# ig-normal-ver12.net
KiCad netlist of a schematic drawn in EAGLE
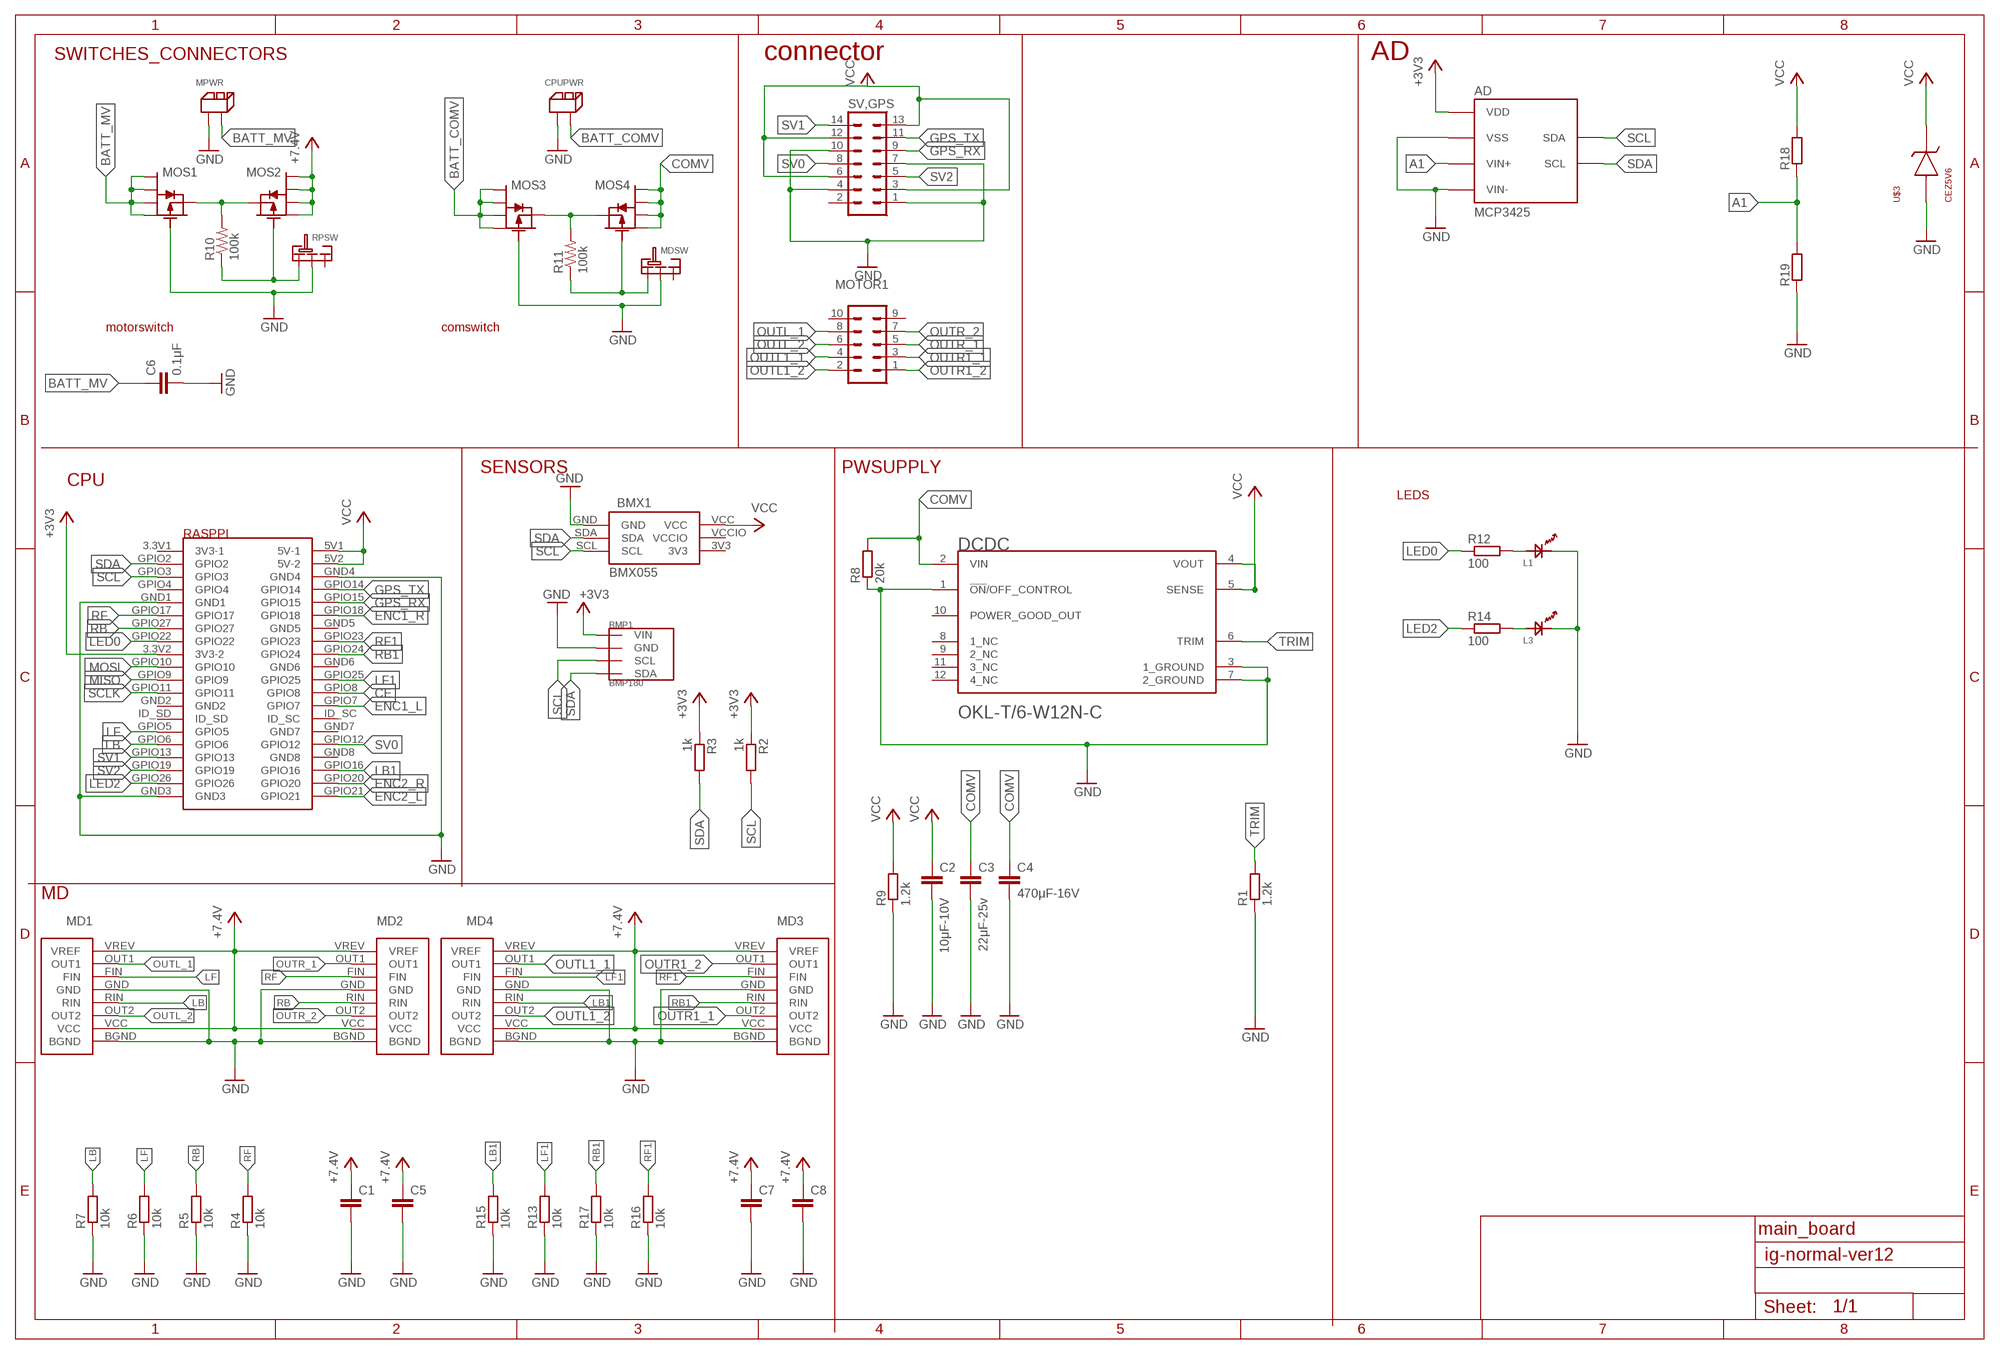
[diagram p0: schematic, sheet 1]

(export (version "E")
  (design (tool "Eeschema 10.0.6"))
  (components
    (comp (ref "AD")
      (value "MCP3425")
      (footprint "eagle-import:SOT23-6")
      (libsource (lib "eagle-import") (part "MCP3425"))
    )
    (comp (ref "BMP1")
      (value "BMP180")
      (footprint "eagle-import:GY-68")
      (libsource (lib "eagle-import") (part "BMP180"))
    )
    (comp (ref "BMX1")
      (value "BMX055")
      (footprint "eagle-import:BMX055")
      (libsource (lib "eagle-import") (part "BMX055"))
    )
    (comp (ref "C1")
      (value "C-EUC0603")
      (footprint "eagle-import:C0603")
      (libsource (lib "eagle-import") (part "C-EUC0603"))
    )
    (comp (ref "C2")
      (value "10μF-10V")
      (footprint "eagle-import:C0603")
      (libsource (lib "eagle-import") (part "C-EUC0603"))
    )
    (comp (ref "C3")
      (value "22μF-25v")
      (footprint "eagle-import:C0805")
      (libsource (lib "eagle-import") (part "C-EUC0805"))
    )
    (comp (ref "C4")
      (value "470μF-16V")
      (footprint "eagle-import:C0603")
      (libsource (lib "eagle-import") (part "C-EUC0603"))
    )
    (comp (ref "C5")
      (value "C-EUC0603")
      (footprint "eagle-import:C0603")
      (libsource (lib "eagle-import") (part "C-EUC0603"))
    )
    (comp (ref "C6")
      (value "0.1μF")
      (footprint "eagle-import:C0603")
      (libsource (lib "eagle-import") (part "C-EUC0603"))
    )
    (comp (ref "C7")
      (value "C-EUC0603")
      (footprint "eagle-import:C0603")
      (libsource (lib "eagle-import") (part "C-EUC0603"))
    )
    (comp (ref "C8")
      (value "C-EUC0603")
      (footprint "eagle-import:C0603")
      (libsource (lib "eagle-import") (part "C-EUC0603"))
    )
    (comp (ref "CPUPWR")
      (value "2PIN")
      (footprint "eagle-import:2PIN")
      (libsource (lib "eagle-import") (part "2PIN"))
    )
    (comp (ref "DCDC")
      (value "OKL-T/6-W12N-CMURATA_OKL-T-6-W12N-C_0_0")
      (footprint "eagle-import:MURATA_OKL-T-6-W12N-C_0")
      (fields
        (field (name "DIGIKEY_PART_NUMBER") "811-2214-1-ND")
        (field (name "MF") "Murata")
        (field (name "MOUSER_PART_NUMBER") "580-OKL-T/6-W12N-C")
      )
      (libsource (lib "eagle-import") (part "OKL-T/6-W12N-CMURATA_OKL-T-6-W12N-C_0_0"))
    )
    (comp (ref "L1")
      (value "OSXX1608C1A")
      (footprint "eagle-import:OSXX1608C1A")
      (libsource (lib "eagle-import") (part "OSXX1608C1A"))
    )
    (comp (ref "L3")
      (value "OSXX1608C1A")
      (footprint "eagle-import:OSXX1608C1A")
      (libsource (lib "eagle-import") (part "OSXX1608C1A"))
    )
    (comp (ref "MD1")
      (value "BD6222HFP-TR")
      (footprint "eagle-import:BD6222HFP-TR")
      (libsource (lib "eagle-import") (part "BD6222HFP-TR"))
    )
    (comp (ref "MD2")
      (value "BD6222HFP-TR")
      (footprint "eagle-import:BD6222HFP-TR")
      (libsource (lib "eagle-import") (part "BD6222HFP-TR"))
    )
    (comp (ref "MD3")
      (value "BD6222HFP-TR")
      (footprint "eagle-import:BD6222HFP-TR")
      (libsource (lib "eagle-import") (part "BD6222HFP-TR"))
    )
    (comp (ref "MD4")
      (value "BD6222HFP-TR")
      (footprint "eagle-import:BD6222HFP-TR")
      (libsource (lib "eagle-import") (part "BD6222HFP-TR"))
    )
    (comp (ref "MDSW")
      (value "SRIDE_SWITCH")
      (footprint "eagle-import:SRIDE_SWITCH")
      (libsource (lib "eagle-import") (part "SRIDE_SWITCH"))
    )
    (comp (ref "MOS1")
      (value "PCH_SSM6J808R")
      (footprint "eagle-import:SSM6J808R")
      (libsource (lib "eagle-import") (part "PCH_SSM6J808R"))
    )
    (comp (ref "MOS2")
      (value "PCH_SSM6J808R")
      (footprint "eagle-import:SSM6J808R")
      (libsource (lib "eagle-import") (part "PCH_SSM6J808R"))
    )
    (comp (ref "MOS3")
      (value "PCH_SSM6J808R")
      (footprint "eagle-import:SSM6J808R")
      (libsource (lib "eagle-import") (part "PCH_SSM6J808R"))
    )
    (comp (ref "MOS4")
      (value "PCH_SSM6J808R")
      (footprint "eagle-import:SSM6J808R")
      (libsource (lib "eagle-import") (part "PCH_SSM6J808R"))
    )
    (comp (ref "MOTOR1")
      (value "ML10L")
      (footprint "eagle-import:ML10L")
      (libsource (lib "eagle-import") (part "ML10L"))
    )
    (comp (ref "MPWR")
      (value "2PIN")
      (footprint "eagle-import:2PIN")
      (libsource (lib "eagle-import") (part "2PIN"))
    )
    (comp (ref "R1")
      (value "1.2k")
      (footprint "eagle-import:R0805")
      (libsource (lib "eagle-import") (part "R-EU_R0805"))
    )
    (comp (ref "R2")
      (value "1k")
      (footprint "eagle-import:R0603")
      (libsource (lib "eagle-import") (part "R-EU_R0603"))
    )
    (comp (ref "R3")
      (value "1k")
      (footprint "eagle-import:R0603")
      (libsource (lib "eagle-import") (part "R-EU_R0603"))
    )
    (comp (ref "R4")
      (value "10k")
      (footprint "eagle-import:R0603")
      (libsource (lib "eagle-import") (part "R-EU_R0603"))
    )
    (comp (ref "R5")
      (value "10k")
      (footprint "eagle-import:R0603")
      (libsource (lib "eagle-import") (part "R-EU_R0603"))
    )
    (comp (ref "R6")
      (value "10k")
      (footprint "eagle-import:R0603")
      (libsource (lib "eagle-import") (part "R-EU_R0603"))
    )
    (comp (ref "R7")
      (value "10k")
      (footprint "eagle-import:R0603")
      (libsource (lib "eagle-import") (part "R-EU_R0603"))
    )
    (comp (ref "R8")
      (value "20k")
      (footprint "eagle-import:R0603")
      (libsource (lib "eagle-import") (part "R-EU_R0603"))
    )
    (comp (ref "R9")
      (value "1.2k")
      (footprint "eagle-import:R0805")
      (libsource (lib "eagle-import") (part "R-EU_R0805"))
    )
    (comp (ref "R10")
      (value "100k")
      (footprint "eagle-import:R0603")
      (libsource (lib "eagle-import") (part "R-US_R0603"))
    )
    (comp (ref "R11")
      (value "100k")
      (footprint "eagle-import:R0603")
      (libsource (lib "eagle-import") (part "R-US_R0603"))
    )
    (comp (ref "R12")
      (value "100")
      (footprint "eagle-import:R0603")
      (libsource (lib "eagle-import") (part "R-EU_R0603"))
    )
    (comp (ref "R13")
      (value "10k")
      (footprint "eagle-import:R0603")
      (libsource (lib "eagle-import") (part "R-EU_R0603"))
    )
    (comp (ref "R14")
      (value "100")
      (footprint "eagle-import:R0603")
      (libsource (lib "eagle-import") (part "R-EU_R0603"))
    )
    (comp (ref "R15")
      (value "10k")
      (footprint "eagle-import:R0603")
      (libsource (lib "eagle-import") (part "R-EU_R0603"))
    )
    (comp (ref "R16")
      (value "10k")
      (footprint "eagle-import:R0603")
      (libsource (lib "eagle-import") (part "R-EU_R0603"))
    )
    (comp (ref "R17")
      (value "10k")
      (footprint "eagle-import:R0603")
      (libsource (lib "eagle-import") (part "R-EU_R0603"))
    )
    (comp (ref "R18")
      (value "R-EU_R0603")
      (footprint "eagle-import:R0603")
      (libsource (lib "eagle-import") (part "R-EU_R0603"))
    )
    (comp (ref "R19")
      (value "R-EU_R0603")
      (footprint "eagle-import:R0603")
      (libsource (lib "eagle-import") (part "R-EU_R0603"))
    )
    (comp (ref "RASPPI")
      (value "RASPBERYPIZEROW")
      (footprint "eagle-import:RASPBERYPIZEROW")
      (libsource (lib "eagle-import") (part "RASPBERYPIZEROW"))
    )
    (comp (ref "RPSW")
      (value "SRIDE_SWITCH")
      (footprint "eagle-import:SRIDE_SWITCH")
      (libsource (lib "eagle-import") (part "SRIDE_SWITCH"))
    )
    (comp (ref "SV,GPS")
      (value "ML14L")
      (footprint "eagle-import:ML14L")
      (libsource (lib "eagle-import") (part "ML14L"))
    )
    (comp (ref "U$3")
      (value "CEZ5V6")
      (footprint "eagle-import:CEZ5V6")
      (libsource (lib "eagle-import") (part "CEZ5V6"))
    )
  )
  (nets
    (net (code "1") (name "+3V3") (class "Default")
      (node (ref "AD") (pin "5") (pinfunction "VDD_5") (pintype "power_in"))
      (node (ref "BMP1") (pin "P1") (pinfunction "VIN_P1") (pintype "bidirectional"))
      (node (ref "R2") (pin "1") (pinfunction "1_1") (pintype "passive"))
      (node (ref "R3") (pin "1") (pinfunction "1_1") (pintype "passive"))
      (node (ref "RASPPI") (pin "3.3V2") (pinfunction "3V3-2_3.3V2") (pintype "bidirectional"))
    )
    (net (code "2") (name "+7.4V") (class "Default")
      (node (ref "C1") (pin "1") (pinfunction "1_1") (pintype "passive"))
      (node (ref "C5") (pin "1") (pinfunction "1_1") (pintype "passive"))
      (node (ref "C7") (pin "1") (pinfunction "1_1") (pintype "passive"))
      (node (ref "C8") (pin "1") (pinfunction "1_1") (pintype "passive"))
      (node (ref "MD1") (pin "VCC") (pinfunction "VCC_VCC") (pintype "bidirectional"))
      (node (ref "MD1") (pin "VREV") (pinfunction "VREF_VREV") (pintype "bidirectional"))
      (node (ref "MD2") (pin "VCC") (pinfunction "VCC_VCC") (pintype "bidirectional"))
      (node (ref "MD2") (pin "VREV") (pinfunction "VREF_VREV") (pintype "bidirectional"))
      (node (ref "MD3") (pin "VCC") (pinfunction "VCC_VCC") (pintype "bidirectional"))
      (node (ref "MD3") (pin "VREV") (pinfunction "VREF_VREV") (pintype "bidirectional"))
      (node (ref "MD4") (pin "VCC") (pinfunction "VCC_VCC") (pintype "bidirectional"))
      (node (ref "MD4") (pin "VREV") (pinfunction "VREF_VREV") (pintype "bidirectional"))
      (node (ref "MOS2") (pin "1") (pinfunction "1_1") (pintype "bidirectional"))
      (node (ref "MOS2") (pin "2") (pinfunction "2_2") (pintype "bidirectional"))
      (node (ref "MOS2") (pin "5") (pinfunction "5_5") (pintype "bidirectional"))
      (node (ref "MOS2") (pin "6") (pinfunction "6_6") (pintype "bidirectional"))
    )
    (net (code "3") (name "/3V3") (class "Default")
      (node (ref "BMX1") (pin "3V3") (pinfunction "3V3_3V3") (pintype "power_in"))
    )
    (net (code "4") (name "/VCCIO") (class "Default")
      (node (ref "BMX1") (pin "VCCIO") (pinfunction "VCCIO_VCCIO") (pintype "power_in"))
    )
    (net (code "5") (name "A1") (class "Default")
      (node (ref "AD") (pin "1") (pinfunction "VIN+_1") (pintype "input"))
      (node (ref "R18") (pin "1") (pinfunction "1_1") (pintype "passive"))
      (node (ref "R19") (pin "2") (pinfunction "2_2") (pintype "passive"))
    )
    (net (code "6") (name "BATT_COMV") (class "Default")
      (node (ref "CPUPWR") (pin "P$2") (pinfunction "P$2_P$2") (pintype "bidirectional"))
      (node (ref "MOS3") (pin "1") (pinfunction "1_1") (pintype "bidirectional"))
      (node (ref "MOS3") (pin "2") (pinfunction "2_2") (pintype "bidirectional"))
      (node (ref "MOS3") (pin "5") (pinfunction "5_5") (pintype "bidirectional"))
      (node (ref "MOS3") (pin "6") (pinfunction "6_6") (pintype "bidirectional"))
    )
    (net (code "7") (name "BATT_MV") (class "Default")
      (node (ref "C6") (pin "1") (pinfunction "1_1") (pintype "passive"))
      (node (ref "MOS1") (pin "1") (pinfunction "1_1") (pintype "bidirectional"))
      (node (ref "MOS1") (pin "2") (pinfunction "2_2") (pintype "bidirectional"))
      (node (ref "MOS1") (pin "5") (pinfunction "5_5") (pintype "bidirectional"))
      (node (ref "MOS1") (pin "6") (pinfunction "6_6") (pintype "bidirectional"))
      (node (ref "MPWR") (pin "P$2") (pinfunction "P$2_P$2") (pintype "bidirectional"))
    )
    (net (code "8") (name "CE") (class "Default")
      (node (ref "RASPPI") (pin "GPIO8") (pinfunction "GPIO8_GPIO8") (pintype "bidirectional"))
    )
    (net (code "9") (name "COMV") (class "Default")
      (node (ref "C3") (pin "1") (pinfunction "1_1") (pintype "passive"))
      (node (ref "C4") (pin "1") (pinfunction "1_1") (pintype "passive"))
      (node (ref "DCDC") (pin "2") (pinfunction "VIN_2") (pintype "bidirectional"))
      (node (ref "MOS4") (pin "1") (pinfunction "1_1") (pintype "bidirectional"))
      (node (ref "MOS4") (pin "2") (pinfunction "2_2") (pintype "bidirectional"))
      (node (ref "MOS4") (pin "5") (pinfunction "5_5") (pintype "bidirectional"))
      (node (ref "MOS4") (pin "6") (pinfunction "6_6") (pintype "bidirectional"))
      (node (ref "R8") (pin "2") (pinfunction "2_2") (pintype "passive"))
    )
    (net (code "10") (name "ENC1_L") (class "Default")
      (node (ref "RASPPI") (pin "GPIO7") (pinfunction "GPIO7_GPIO7") (pintype "bidirectional"))
    )
    (net (code "11") (name "ENC1_R") (class "Default")
      (node (ref "RASPPI") (pin "GPIO18") (pinfunction "GPIO18_GPIO18") (pintype "bidirectional"))
    )
    (net (code "12") (name "ENC2_L") (class "Default")
      (node (ref "RASPPI") (pin "GPIO21") (pinfunction "GPIO21_GPIO21") (pintype "bidirectional"))
    )
    (net (code "13") (name "ENC2_R") (class "Default")
      (node (ref "RASPPI") (pin "GPIO20") (pinfunction "GPIO20_GPIO20") (pintype "bidirectional"))
    )
    (net (code "14") (name "GND") (class "Default")
      (node (ref "AD") (pin "2") (pinfunction "VSS_2") (pintype "power_in"))
      (node (ref "AD") (pin "6") (pinfunction "VIN-_6") (pintype "input"))
      (node (ref "BMP1") (pin "P2") (pinfunction "GND_P2") (pintype "bidirectional"))
      (node (ref "BMX1") (pin "GND") (pinfunction "GND_GND") (pintype "power_in"))
      (node (ref "C1") (pin "2") (pinfunction "2_2") (pintype "passive"))
      (node (ref "C2") (pin "2") (pinfunction "2_2") (pintype "passive"))
      (node (ref "C3") (pin "2") (pinfunction "2_2") (pintype "passive"))
      (node (ref "C4") (pin "2") (pinfunction "2_2") (pintype "passive"))
      (node (ref "C5") (pin "2") (pinfunction "2_2") (pintype "passive"))
      (node (ref "C6") (pin "2") (pinfunction "2_2") (pintype "passive"))
      (node (ref "C7") (pin "2") (pinfunction "2_2") (pintype "passive"))
      (node (ref "C8") (pin "2") (pinfunction "2_2") (pintype "passive"))
      (node (ref "CPUPWR") (pin "P$1") (pinfunction "P$1_P$1") (pintype "bidirectional"))
      (node (ref "DCDC") (pin "1") (pinfunction "~{ON}/OFF_CONTROL_1") (pintype "bidirectional"))
      (node (ref "DCDC") (pin "3") (pinfunction "1_GROUND_3") (pintype "power_in"))
      (node (ref "DCDC") (pin "7") (pinfunction "2_GROUND_7") (pintype "power_in"))
      (node (ref "L1") (pin "CT") (pinfunction "CT_CT") (pintype "bidirectional"))
      (node (ref "L3") (pin "CT") (pinfunction "CT_CT") (pintype "bidirectional"))
      (node (ref "MD1") (pin "BGND") (pinfunction "BGND_BGND") (pintype "bidirectional"))
      (node (ref "MD1") (pin "GND") (pinfunction "GND_GND") (pintype "bidirectional"))
      (node (ref "MD2") (pin "BGND") (pinfunction "BGND_BGND") (pintype "bidirectional"))
      (node (ref "MD2") (pin "GND") (pinfunction "GND_GND") (pintype "bidirectional"))
      (node (ref "MD3") (pin "BGND") (pinfunction "BGND_BGND") (pintype "bidirectional"))
      (node (ref "MD3") (pin "GND") (pinfunction "GND_GND") (pintype "bidirectional"))
      (node (ref "MD4") (pin "BGND") (pinfunction "BGND_BGND") (pintype "bidirectional"))
      (node (ref "MD4") (pin "GND") (pinfunction "GND_GND") (pintype "bidirectional"))
      (node (ref "MDSW") (pin "LR") (pinfunction "LR_LR") (pintype "bidirectional"))
      (node (ref "MOS1") (pin "3") (pinfunction "3_3") (pintype "bidirectional"))
      (node (ref "MOS3") (pin "3") (pinfunction "3_3") (pintype "bidirectional"))
      (node (ref "MPWR") (pin "P$1") (pinfunction "P$1_P$1") (pintype "bidirectional"))
      (node (ref "R1") (pin "1") (pinfunction "1_1") (pintype "passive"))
      (node (ref "R13") (pin "1") (pinfunction "1_1") (pintype "passive"))
      (node (ref "R15") (pin "1") (pinfunction "1_1") (pintype "passive"))
      (node (ref "R16") (pin "1") (pinfunction "1_1") (pintype "passive"))
      (node (ref "R17") (pin "1") (pinfunction "1_1") (pintype "passive"))
      (node (ref "R19") (pin "1") (pinfunction "1_1") (pintype "passive"))
      (node (ref "R4") (pin "1") (pinfunction "1_1") (pintype "passive"))
      (node (ref "R5") (pin "1") (pinfunction "1_1") (pintype "passive"))
      (node (ref "R6") (pin "1") (pinfunction "1_1") (pintype "passive"))
      (node (ref "R7") (pin "1") (pinfunction "1_1") (pintype "passive"))
      (node (ref "R8") (pin "1") (pinfunction "1_1") (pintype "passive"))
      (node (ref "R9") (pin "1") (pinfunction "1_1") (pintype "passive"))
      (node (ref "RASPPI") (pin "GND1") (pinfunction "GND1_GND1") (pintype "bidirectional"))
      (node (ref "RASPPI") (pin "GND3") (pinfunction "GND3_GND3") (pintype "bidirectional"))
      (node (ref "RASPPI") (pin "GND4") (pinfunction "GND4_GND4") (pintype "bidirectional"))
      (node (ref "RPSW") (pin "LR") (pinfunction "LR_LR") (pintype "bidirectional"))
      (node (ref "SV,GPS") (pin "1") (pinfunction "1_1") (pintype "passive"))
      (node (ref "SV,GPS") (pin "10") (pinfunction "10_10") (pintype "passive"))
      (node (ref "SV,GPS") (pin "4") (pinfunction "4_4") (pintype "passive"))
      (node (ref "SV,GPS") (pin "7") (pinfunction "7_7") (pintype "passive"))
      (node (ref "U$3") (pin "P$1") (pinfunction "P$1_P$1") (pintype "bidirectional"))
    )
    (net (code "15") (name "GPS_RX") (class "Default")
      (node (ref "RASPPI") (pin "GPIO15") (pinfunction "GPIO15_GPIO15") (pintype "bidirectional"))
      (node (ref "SV,GPS") (pin "9") (pinfunction "9_9") (pintype "passive"))
    )
    (net (code "16") (name "GPS_TX") (class "Default")
      (node (ref "RASPPI") (pin "GPIO14") (pinfunction "GPIO14_GPIO14") (pintype "bidirectional"))
      (node (ref "SV,GPS") (pin "11") (pinfunction "11_11") (pintype "passive"))
    )
    (net (code "17") (name "LB") (class "Default")
      (node (ref "MD1") (pin "RIN") (pinfunction "RIN_RIN") (pintype "bidirectional"))
      (node (ref "R7") (pin "2") (pinfunction "2_2") (pintype "passive"))
      (node (ref "RASPPI") (pin "GPIO6") (pinfunction "GPIO6_GPIO6") (pintype "bidirectional"))
    )
    (net (code "18") (name "LB1") (class "Default")
      (node (ref "MD4") (pin "RIN") (pinfunction "RIN_RIN") (pintype "bidirectional"))
      (node (ref "R15") (pin "2") (pinfunction "2_2") (pintype "passive"))
      (node (ref "RASPPI") (pin "GPIO16") (pinfunction "GPIO16_GPIO16") (pintype "bidirectional"))
    )
    (net (code "19") (name "LED0") (class "Default")
      (node (ref "R12") (pin "1") (pinfunction "1_1") (pintype "passive"))
      (node (ref "RASPPI") (pin "GPIO22") (pinfunction "GPIO22_GPIO22") (pintype "bidirectional"))
    )
    (net (code "20") (name "LED2") (class "Default")
      (node (ref "R14") (pin "1") (pinfunction "1_1") (pintype "passive"))
      (node (ref "RASPPI") (pin "GPIO26") (pinfunction "GPIO26_GPIO26") (pintype "bidirectional"))
    )
    (net (code "21") (name "LF") (class "Default")
      (node (ref "MD1") (pin "FIN") (pinfunction "FIN_FIN") (pintype "bidirectional"))
      (node (ref "R6") (pin "2") (pinfunction "2_2") (pintype "passive"))
      (node (ref "RASPPI") (pin "GPIO5") (pinfunction "GPIO5_GPIO5") (pintype "bidirectional"))
    )
    (net (code "22") (name "LF1") (class "Default")
      (node (ref "MD4") (pin "FIN") (pinfunction "FIN_FIN") (pintype "bidirectional"))
      (node (ref "R13") (pin "2") (pinfunction "2_2") (pintype "passive"))
      (node (ref "RASPPI") (pin "GPIO25") (pinfunction "GPIO25_GPIO25") (pintype "bidirectional"))
    )
    (net (code "23") (name "MISO") (class "Default")
      (node (ref "RASPPI") (pin "GPIO9") (pinfunction "GPIO9_GPIO9") (pintype "bidirectional"))
    )
    (net (code "24") (name "MOSI") (class "Default")
      (node (ref "RASPPI") (pin "GPIO10") (pinfunction "GPIO10_GPIO10") (pintype "bidirectional"))
    )
    (net (code "25") (name "Net-(L1-PadAN)") (class "Default")
      (node (ref "L1") (pin "AN") (pinfunction "AN_AN") (pintype "bidirectional"))
      (node (ref "R12") (pin "2") (pinfunction "2_2") (pintype "passive"))
    )
    (net (code "26") (name "Net-(L3-PadAN)") (class "Default")
      (node (ref "L3") (pin "AN") (pinfunction "AN_AN") (pintype "bidirectional"))
      (node (ref "R14") (pin "2") (pinfunction "2_2") (pintype "passive"))
    )
    (net (code "27") (name "Net-(MDSW-PadL)") (class "Default")
      (node (ref "MDSW") (pin "L") (pinfunction "L_L") (pintype "bidirectional"))
      (node (ref "MOS4") (pin "3") (pinfunction "3_3") (pintype "bidirectional"))
      (node (ref "R11") (pin "1") (pinfunction "1_1") (pintype "passive"))
    )
    (net (code "28") (name "Net-(MOS1-Pad4)") (class "Default")
      (node (ref "MOS1") (pin "4") (pinfunction "4_4") (pintype "bidirectional"))
      (node (ref "MOS2") (pin "4") (pinfunction "4_4") (pintype "bidirectional"))
      (node (ref "R10") (pin "2") (pinfunction "2_2") (pintype "passive"))
    )
    (net (code "29") (name "Net-(MOS2-Pad3)") (class "Default")
      (node (ref "MOS2") (pin "3") (pinfunction "3_3") (pintype "bidirectional"))
      (node (ref "R10") (pin "1") (pinfunction "1_1") (pintype "passive"))
      (node (ref "RPSW") (pin "L") (pinfunction "L_L") (pintype "bidirectional"))
    )
    (net (code "30") (name "Net-(MOS3-Pad4)") (class "Default")
      (node (ref "MOS3") (pin "4") (pinfunction "4_4") (pintype "bidirectional"))
      (node (ref "MOS4") (pin "4") (pinfunction "4_4") (pintype "bidirectional"))
      (node (ref "R11") (pin "2") (pinfunction "2_2") (pintype "passive"))
    )
    (net (code "31") (name "OUTL1_1") (class "Default")
      (node (ref "MD4") (pin "OUT1") (pinfunction "OUT1_OUT1") (pintype "bidirectional"))
      (node (ref "MOTOR1") (pin "4") (pinfunction "4_4") (pintype "passive"))
    )
    (net (code "32") (name "OUTL1_2") (class "Default")
      (node (ref "MD4") (pin "OUT2") (pinfunction "OUT2_OUT2") (pintype "bidirectional"))
      (node (ref "MOTOR1") (pin "2") (pinfunction "2_2") (pintype "passive"))
    )
    (net (code "33") (name "OUTL_1") (class "Default")
      (node (ref "MD1") (pin "OUT1") (pinfunction "OUT1_OUT1") (pintype "bidirectional"))
      (node (ref "MOTOR1") (pin "8") (pinfunction "8_8") (pintype "passive"))
    )
    (net (code "34") (name "OUTL_2") (class "Default")
      (node (ref "MD1") (pin "OUT2") (pinfunction "OUT2_OUT2") (pintype "bidirectional"))
      (node (ref "MOTOR1") (pin "6") (pinfunction "6_6") (pintype "passive"))
    )
    (net (code "35") (name "OUTR1_1") (class "Default")
      (node (ref "MD3") (pin "OUT2") (pinfunction "OUT2_OUT2") (pintype "bidirectional"))
      (node (ref "MOTOR1") (pin "3") (pinfunction "3_3") (pintype "passive"))
    )
    (net (code "36") (name "OUTR1_2") (class "Default")
      (node (ref "MD3") (pin "OUT1") (pinfunction "OUT1_OUT1") (pintype "bidirectional"))
      (node (ref "MOTOR1") (pin "1") (pinfunction "1_1") (pintype "passive"))
    )
    (net (code "37") (name "OUTR_1") (class "Default")
      (node (ref "MD2") (pin "OUT1") (pinfunction "OUT1_OUT1") (pintype "bidirectional"))
      (node (ref "MOTOR1") (pin "5") (pinfunction "5_5") (pintype "passive"))
    )
    (net (code "38") (name "OUTR_2") (class "Default")
      (node (ref "MD2") (pin "OUT2") (pinfunction "OUT2_OUT2") (pintype "bidirectional"))
      (node (ref "MOTOR1") (pin "7") (pinfunction "7_7") (pintype "passive"))
    )
    (net (code "39") (name "RB") (class "Default")
      (node (ref "MD2") (pin "RIN") (pinfunction "RIN_RIN") (pintype "bidirectional"))
      (node (ref "R5") (pin "2") (pinfunction "2_2") (pintype "passive"))
      (node (ref "RASPPI") (pin "GPIO27") (pinfunction "GPIO27_GPIO27") (pintype "bidirectional"))
    )
    (net (code "40") (name "RB1") (class "Default")
      (node (ref "MD3") (pin "RIN") (pinfunction "RIN_RIN") (pintype "bidirectional"))
      (node (ref "R17") (pin "2") (pinfunction "2_2") (pintype "passive"))
      (node (ref "RASPPI") (pin "GPIO24") (pinfunction "GPIO24_GPIO24") (pintype "bidirectional"))
    )
    (net (code "41") (name "RF") (class "Default")
      (node (ref "MD2") (pin "FIN") (pinfunction "FIN_FIN") (pintype "bidirectional"))
      (node (ref "R4") (pin "2") (pinfunction "2_2") (pintype "passive"))
      (node (ref "RASPPI") (pin "GPIO17") (pinfunction "GPIO17_GPIO17") (pintype "bidirectional"))
    )
    (net (code "42") (name "RF1") (class "Default")
      (node (ref "MD3") (pin "FIN") (pinfunction "FIN_FIN") (pintype "bidirectional"))
      (node (ref "R16") (pin "2") (pinfunction "2_2") (pintype "passive"))
      (node (ref "RASPPI") (pin "GPIO23") (pinfunction "GPIO23_GPIO23") (pintype "bidirectional"))
    )
    (net (code "43") (name "SCL") (class "Default")
      (node (ref "AD") (pin "4") (pinfunction "SDA_4") (pintype "bidirectional"))
      (node (ref "BMP1") (pin "P3") (pinfunction "SCL_P3") (pintype "bidirectional"))
      (node (ref "BMX1") (pin "SCL") (pinfunction "SCL_SCL") (pintype "bidirectional"))
      (node (ref "R2") (pin "2") (pinfunction "2_2") (pintype "passive"))
      (node (ref "RASPPI") (pin "GPIO3") (pinfunction "GPIO3_GPIO3") (pintype "bidirectional"))
    )
    (net (code "44") (name "SCLK") (class "Default")
      (node (ref "RASPPI") (pin "GPIO11") (pinfunction "GPIO11_GPIO11") (pintype "bidirectional"))
    )
    (net (code "45") (name "SDA") (class "Default")
      (node (ref "AD") (pin "3") (pinfunction "SCL_3") (pintype "bidirectional"))
      (node (ref "BMP1") (pin "P4") (pinfunction "SDA_P4") (pintype "bidirectional"))
      (node (ref "BMX1") (pin "SDA") (pinfunction "SDA_SDA") (pintype "bidirectional"))
      (node (ref "R3") (pin "2") (pinfunction "2_2") (pintype "passive"))
      (node (ref "RASPPI") (pin "GPIO2") (pinfunction "GPIO2_GPIO2") (pintype "bidirectional"))
    )
    (net (code "46") (name "SV0") (class "Default")
      (node (ref "RASPPI") (pin "GPIO12") (pinfunction "GPIO12_GPIO12") (pintype "bidirectional"))
      (node (ref "SV,GPS") (pin "8") (pinfunction "8_8") (pintype "passive"))
    )
    (net (code "47") (name "SV1") (class "Default")
      (node (ref "RASPPI") (pin "GPIO13") (pinfunction "GPIO13_GPIO13") (pintype "bidirectional"))
      (node (ref "SV,GPS") (pin "14") (pinfunction "14_14") (pintype "passive"))
    )
    (net (code "48") (name "SV2") (class "Default")
      (node (ref "RASPPI") (pin "GPIO19") (pinfunction "GPIO19_GPIO19") (pintype "bidirectional"))
      (node (ref "SV,GPS") (pin "5") (pinfunction "5_5") (pintype "passive"))
    )
    (net (code "49") (name "TRIM") (class "Default")
      (node (ref "DCDC") (pin "6") (pinfunction "TRIM_6") (pintype "passive"))
      (node (ref "R1") (pin "2") (pinfunction "2_2") (pintype "passive"))
    )
    (net (code "50") (name "VCC") (class "Default")
      (node (ref "BMX1") (pin "VCC") (pinfunction "VCC_VCC") (pintype "power_in"))
      (node (ref "C2") (pin "1") (pinfunction "1_1") (pintype "passive"))
      (node (ref "DCDC") (pin "4") (pinfunction "VOUT_4") (pintype "bidirectional"))
      (node (ref "DCDC") (pin "5") (pinfunction "SENSE_5") (pintype "passive"))
      (node (ref "R18") (pin "2") (pinfunction "2_2") (pintype "passive"))
      (node (ref "R9") (pin "2") (pinfunction "2_2") (pintype "passive"))
      (node (ref "RASPPI") (pin "5V1") (pinfunction "5V-1_5V1") (pintype "bidirectional"))
      (node (ref "RASPPI") (pin "5V2") (pinfunction "5V-2_5V2") (pintype "bidirectional"))
      (node (ref "SV,GPS") (pin "12") (pinfunction "12_12") (pintype "passive"))
      (node (ref "SV,GPS") (pin "13") (pinfunction "13_13") (pintype "passive"))
      (node (ref "SV,GPS") (pin "3") (pinfunction "3_3") (pintype "passive"))
      (node (ref "SV,GPS") (pin "6") (pinfunction "6_6") (pintype "passive"))
      (node (ref "U$3") (pin "P$2") (pinfunction "P$2_P$2") (pintype "bidirectional"))
    )
    (net (code "51") (name "unconnected-(DCDC-1_NC-Pad8)") (class "Default")
      (node (ref "DCDC") (pin "8") (pinfunction "1_NC_8") (pintype "passive"))
    )
    (net (code "52") (name "unconnected-(DCDC-2_NC-Pad9)") (class "Default")
      (node (ref "DCDC") (pin "9") (pinfunction "2_NC_9") (pintype "passive"))
    )
    (net (code "53") (name "unconnected-(DCDC-3_NC-Pad11)") (class "Default")
      (node (ref "DCDC") (pin "11") (pinfunction "3_NC_11") (pintype "passive"))
    )
    (net (code "54") (name "unconnected-(DCDC-4_NC-Pad12)") (class "Default")
      (node (ref "DCDC") (pin "12") (pinfunction "4_NC_12") (pintype "passive"))
    )
    (net (code "55") (name "unconnected-(DCDC-POWER_GOOD_OUT-Pad10)") (class "Default")
      (node (ref "DCDC") (pin "10") (pinfunction "POWER_GOOD_OUT_10") (pintype "open_collector"))
    )
    (net (code "56") (name "unconnected-(MDSW-PadR)") (class "Default")
      (node (ref "MDSW") (pin "R") (pinfunction "R_R") (pintype "bidirectional"))
    )
    (net (code "57") (name "unconnected-(MOTOR1-Pad9)") (class "Default")
      (node (ref "MOTOR1") (pin "9") (pinfunction "9_9") (pintype "passive"))
    )
    (net (code "58") (name "unconnected-(MOTOR1-Pad10)") (class "Default")
      (node (ref "MOTOR1") (pin "10") (pinfunction "10_10") (pintype "passive"))
    )
    (net (code "59") (name "unconnected-(RASPPI-3V3-1-Pad3.3V1)") (class "Default")
      (node (ref "RASPPI") (pin "3.3V1") (pinfunction "3V3-1_3.3V1") (pintype "bidirectional"))
    )
    (net (code "60") (name "unconnected-(RASPPI-PadGND2)") (class "Default")
      (node (ref "RASPPI") (pin "GND2") (pinfunction "GND2_GND2") (pintype "bidirectional"))
    )
    (net (code "61") (name "unconnected-(RASPPI-PadGND5)") (class "Default")
      (node (ref "RASPPI") (pin "GND5") (pinfunction "GND5_GND5") (pintype "bidirectional"))
    )
    (net (code "62") (name "unconnected-(RASPPI-PadGND6)") (class "Default")
      (node (ref "RASPPI") (pin "GND6") (pinfunction "GND6_GND6") (pintype "bidirectional"))
    )
    (net (code "63") (name "unconnected-(RASPPI-PadGND7)") (class "Default")
      (node (ref "RASPPI") (pin "GND7") (pinfunction "GND7_GND7") (pintype "bidirectional"))
    )
    (net (code "64") (name "unconnected-(RASPPI-PadGND8)") (class "Default")
      (node (ref "RASPPI") (pin "GND8") (pinfunction "GND8_GND8") (pintype "bidirectional"))
    )
    (net (code "65") (name "unconnected-(RASPPI-PadGPIO4)") (class "Default")
      (node (ref "RASPPI") (pin "GPIO4") (pinfunction "GPIO4_GPIO4") (pintype "bidirectional"))
    )
    (net (code "66") (name "unconnected-(RASPPI-PadID_SC)") (class "Default")
      (node (ref "RASPPI") (pin "ID_SC") (pinfunction "ID_SC_ID_SC") (pintype "bidirectional"))
    )
    (net (code "67") (name "unconnected-(RASPPI-PadID_SD)") (class "Default")
      (node (ref "RASPPI") (pin "ID_SD") (pinfunction "ID_SD_ID_SD") (pintype "bidirectional"))
    )
    (net (code "68") (name "unconnected-(RPSW-PadR)") (class "Default")
      (node (ref "RPSW") (pin "R") (pinfunction "R_R") (pintype "bidirectional"))
    )
    (net (code "69") (name "unconnected-(SV,GPS-Pad2)") (class "Default")
      (node (ref "SV,GPS") (pin "2") (pinfunction "2_2") (pintype "passive"))
    )
  )
)
